# SprinKlr-8_Rev1.net
KiCad netlist of a schematic drawn in EasyEDA Pro
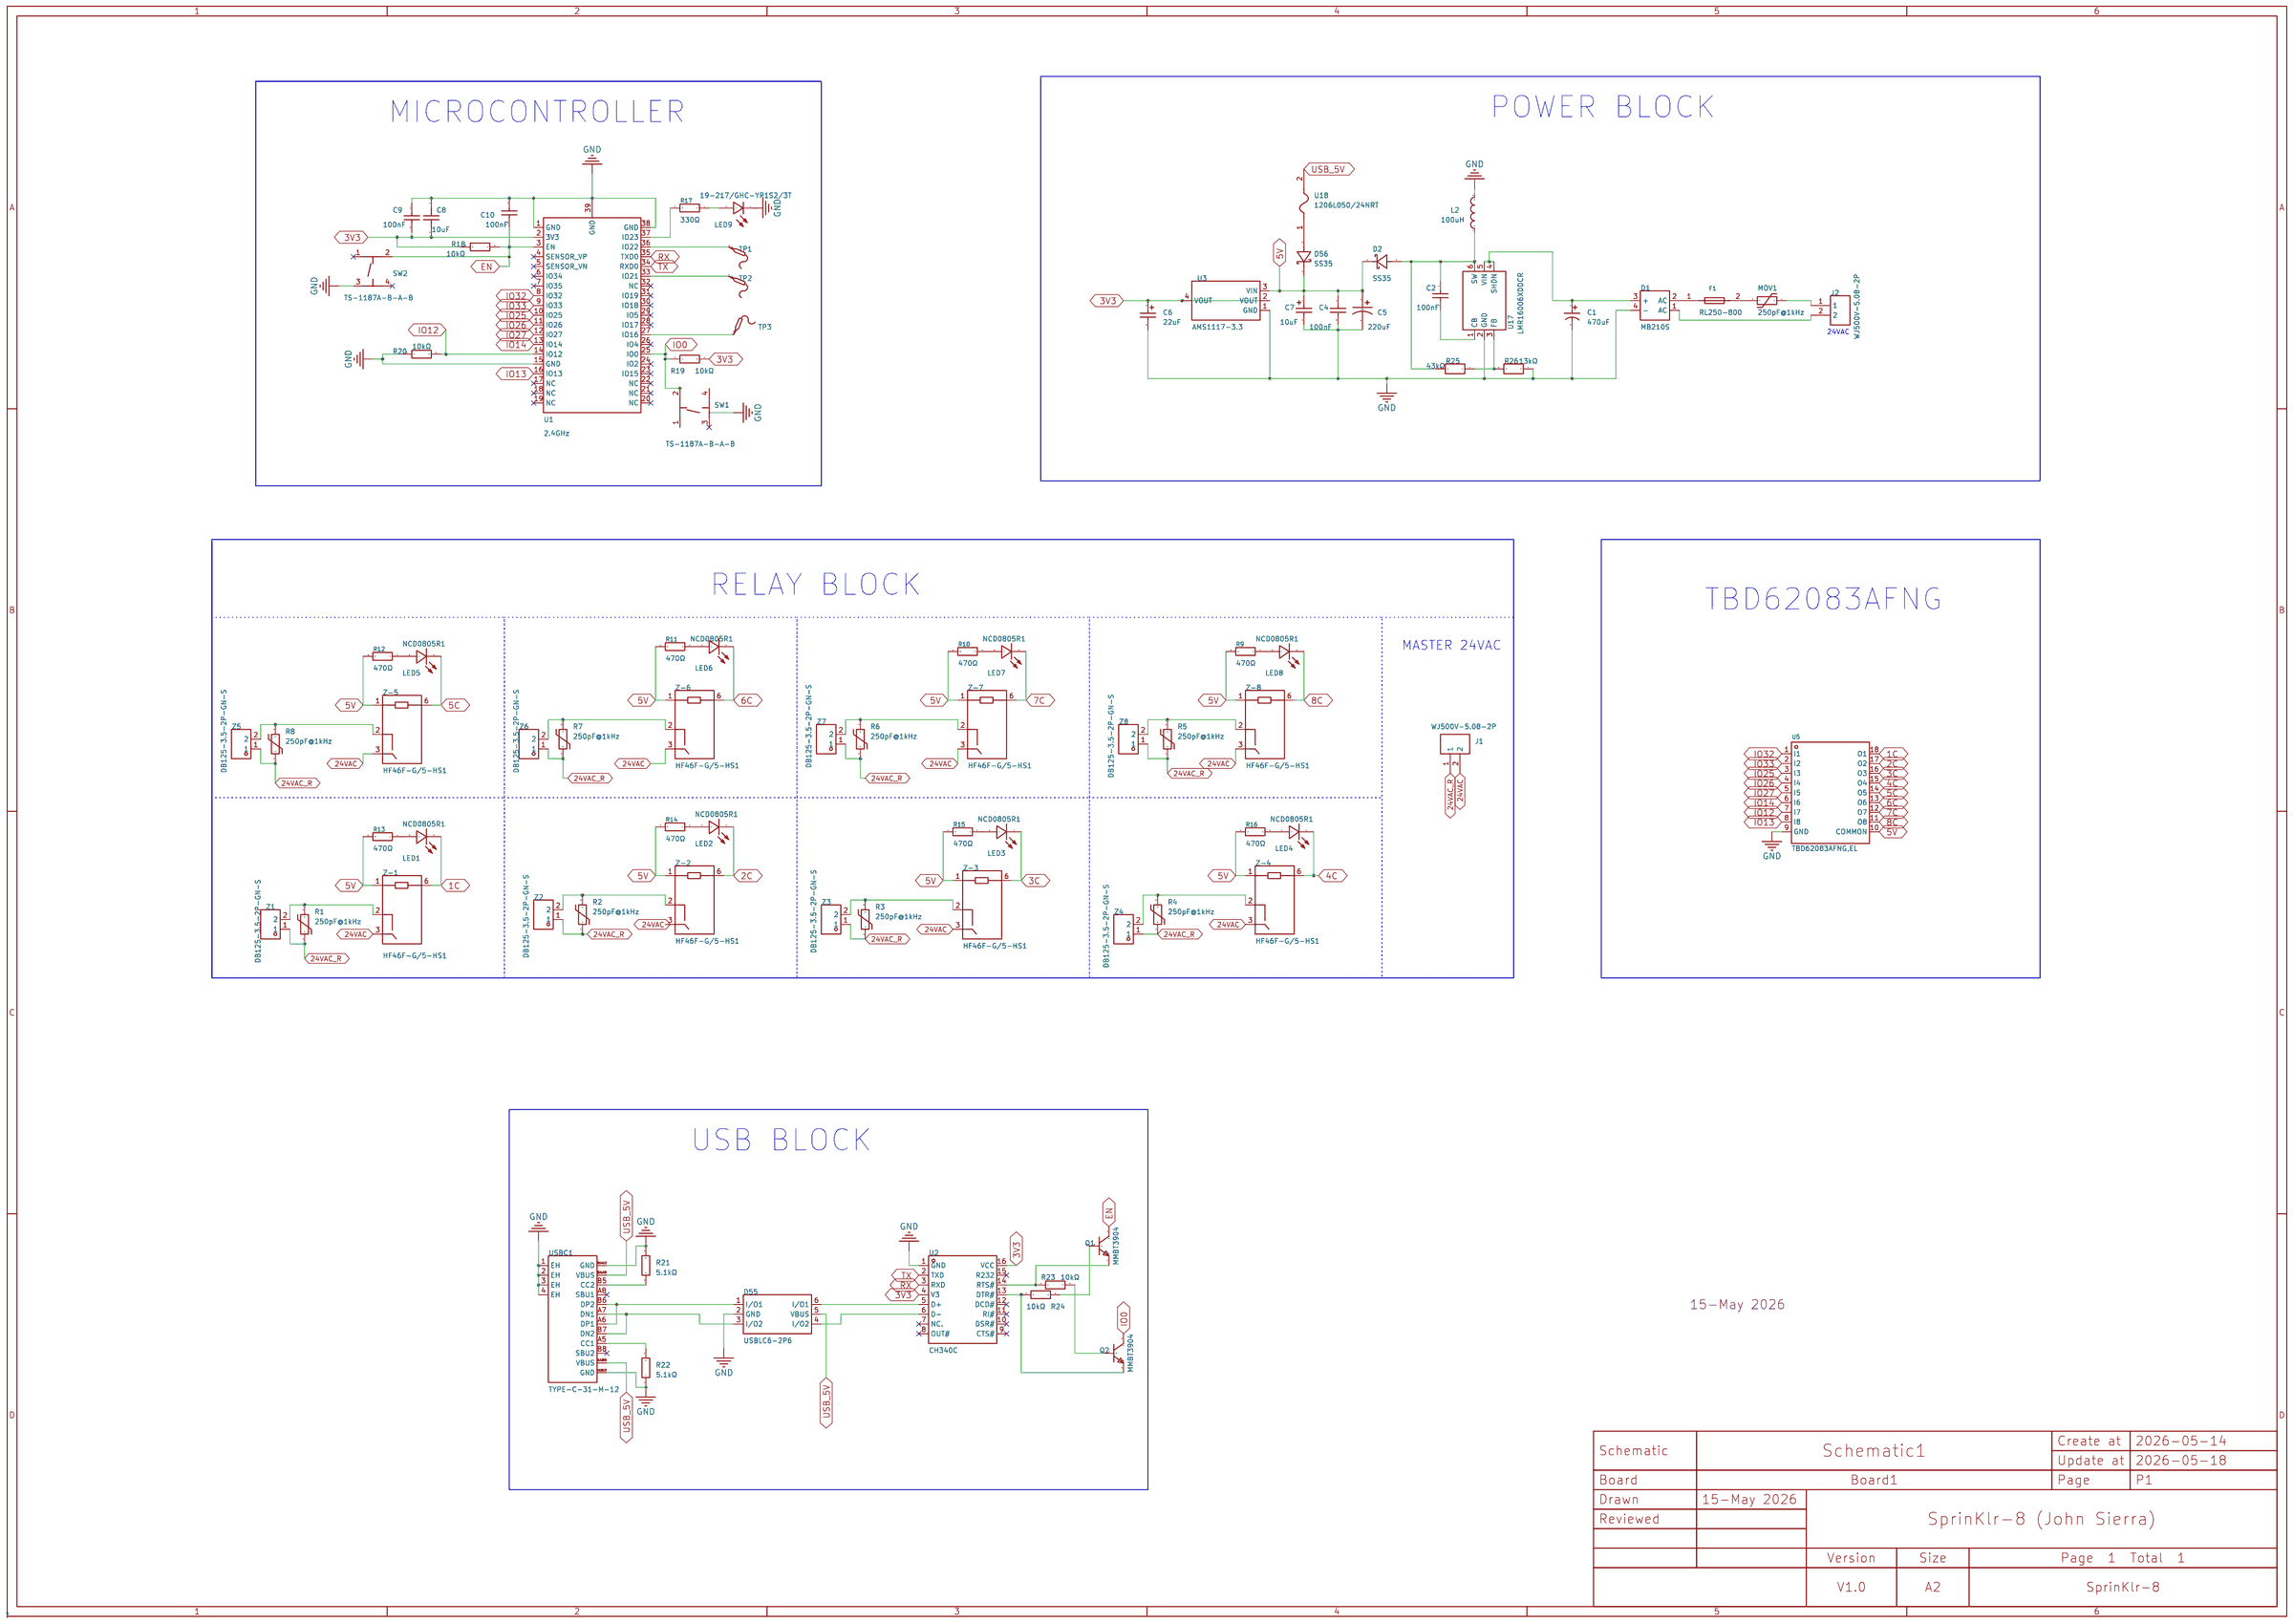
[diagram p0: schematic sheet]

(export (version "E")
  (design (tool "Eeschema 10.0.6"))
  (components
    (comp (ref "C1")
      (value "470uF")
      (footprint "easyedapro:CAP-TH_BD13.0-P5.00-D1.2-FD")
      (fields (field (name "Manufacturer Part") "ERF1HM471K16OT") (field (name "Manufacturer") "AISHI(艾华集团)"))
      (libsource (lib "easyedapro") (part "ERF1HM471K16OT"))
    )
    (comp (ref "C2")
      (value "100nF")
      (footprint "easyedapro:C0805")
      (description "Capacitance:100nF Tolerance:±10% Tolerance:±10% Voltage Rating:100V Temperature Coefficient:X7R")
      (fields
        (field (name "Manufacturer Part") "CL21B104KCFNNNE")
        (field (name "Manufacturer") "SAMSUNG(三星)")
      )
      (libsource (lib "easyedapro") (part "CL21B104KCFNNNE"))
    )
    (comp (ref "C4")
      (value "100nF")
      (footprint "easyedapro:C0805")
      (fields
        (field (name "Manufacturer Part") "CL21B104KCFNNNE")
        (field (name "Manufacturer") "SAMSUNG(三星)")
      )
      (libsource (lib "easyedapro") (part "CL21B104KCFNNNE"))
    )
    (comp (ref "C5")
      (value "220uF")
      (footprint "easyedapro:CAP-TH_BD10.0-P5.00-D1.0-FD")
      (fields
        (field (name "Manufacturer Part") "SHG220UF50V01EC1210")
        (field (name "Manufacturer") "KNSCHA(科尼盛)")
      )
      (libsource (lib "easyedapro") (part "SHG220UF50V01EC1210"))
    )
    (comp (ref "C6")
      (value "22uF")
      (footprint "easyedapro:CASE-A_3216")
      (fields (field (name "Manufacturer Part") "TAJA226K010RNJ") (field (name "Manufacturer") "Kyocera AVX"))
      (libsource (lib "easyedapro") (part "TAJA226K010RNJ"))
    )
    (comp (ref "C7")
      (value "10uF")
      (footprint "easyedapro:CAP-SMD_L3.2-W1.6-RD-C7171")
      (fields (field (name "Manufacturer Part") "TAJA106K016RNJ") (field (name "Manufacturer") "Kyocera AVX"))
      (libsource (lib "easyedapro") (part "TAJA106K016RNJ"))
    )
    (comp (ref "C8")
      (value "10uF")
      (footprint "easyedapro:C0805")
      (fields
        (field (name "Manufacturer Part") "CL21A106KAYNNNE")
        (field (name "Manufacturer") "SAMSUNG(三星)")
      )
      (libsource (lib "easyedapro") (part "CL21A106KAYNNNE"))
    )
    (comp (ref "C9")
      (value "100nF")
      (footprint "easyedapro:C0805")
      (fields
        (field (name "Manufacturer Part") "CL21B104KCFNNNE")
        (field (name "Manufacturer") "SAMSUNG(三星)")
      )
      (libsource (lib "easyedapro") (part "CL21B104KCFNNNE"))
    )
    (comp (ref "C10")
      (value "100nF")
      (footprint "easyedapro:C0805")
      (fields
        (field (name "Manufacturer Part") "CL21B104KCFNNNE")
        (field (name "Manufacturer") "SAMSUNG(三星)")
      )
      (libsource (lib "easyedapro") (part "CL21B104KCFNNNE"))
    )
    (comp (ref "D1")
      (value "MB210S")
      (footprint "easyedapro:MBS_L4.7-W4.0-P2.50-LS7.0-BL")
      (fields (field (name "Manufacturer") "晶导微电子"))
      (libsource (lib "easyedapro") (part "MB210S"))
    )
    (comp (ref "D2")
      (value "SS35")
      (footprint "easyedapro:SMC_L6.9-W5.9-LS7.9-RD")
      (fields (field (name "Manufacturer") "onsemi(安森美)"))
      (libsource (lib "easyedapro") (part "SS35"))
    )
    (comp (ref "D55")
      (value "USBLC6-2P6")
      (footprint "easyedapro:SOT-666-6_L1.6-W1.2-P0.50-LS1.6-BL")
      (fields (field (name "Manufacturer") "TECH PUBLIC(台舟)"))
      (libsource (lib "easyedapro") (part "USBLC6-2P6_C2827693"))
    )
    (comp (ref "D56")
      (value "SS35")
      (footprint "easyedapro:SMC_L6.9-W5.9-LS7.9-RD")
      (fields (field (name "Manufacturer") "onsemi(安森美)"))
      (libsource (lib "easyedapro") (part "SS35"))
    )
    (comp (ref "F1")
      (value "RL250-800")
      (footprint "easyedapro:FUSE-TH_L20.0-W4.5-P5.10-D0.8-S3.70")
      (fields (field (name "Manufacturer") "RUILON(瑞隆源)"))
      (libsource (lib "easyedapro") (part "RL250-800"))
    )
    (comp (ref "J1")
      (value "WJ500V-5.08-2P")
      (footprint "easyedapro:CONN-TH_2P-P5.00_WJ500V-5.08-2P")
      (fields (field (name "Manufacturer") "KANGNEX(康奈克斯电气)"))
      (libsource (lib "easyedapro") (part "WJ500V-5.08-2P-14-00A"))
    )
    (comp (ref "J2")
      (value "WJ500V-5.08-2P")
      (footprint "easyedapro:CONN-TH_2P-P5.00_WJ500V-5.08-2P")
      (fields (field (name "Manufacturer") "KANGNEX(康奈克斯电气)"))
      (libsource (lib "easyedapro") (part "WJ500V-5.08-2P-14-00A"))
    )
    (comp (ref "L2")
      (value "100uH")
      (footprint "easyedapro:IND-SMD_L11.5-W10.0")
      (fields
        (field (name "Manufacturer Part") "PSPMAA1050H-101M-ANP")
        (field (name "Manufacturer") "PROD(谱罗德)")
      )
      (libsource (lib "easyedapro") (part "PSPMAA1050H-101M-ANP"))
    )
    (comp (ref "LED1")
      (value "NCD0805R1")
      (footprint "easyedapro:LED0805-RD")
      (fields (field (name "Manufacturer") "国星光电"))
      (libsource (lib "easyedapro") (part "FC-2012HRK-620D"))
    )
    (comp (ref "LED2")
      (value "NCD0805R1")
      (footprint "easyedapro:LED0805-RD")
      (fields (field (name "Manufacturer") "国星光电"))
      (libsource (lib "easyedapro") (part "FC-2012HRK-620D"))
    )
    (comp (ref "LED3")
      (value "NCD0805R1")
      (footprint "easyedapro:LED0805-RD")
      (fields (field (name "Manufacturer") "国星光电"))
      (libsource (lib "easyedapro") (part "FC-2012HRK-620D"))
    )
    (comp (ref "LED4")
      (value "NCD0805R1")
      (footprint "easyedapro:LED0805-RD")
      (fields (field (name "Manufacturer") "国星光电"))
      (libsource (lib "easyedapro") (part "FC-2012HRK-620D"))
    )
    (comp (ref "LED5")
      (value "NCD0805R1")
      (footprint "easyedapro:LED0805-RD")
      (fields (field (name "Manufacturer") "国星光电"))
      (libsource (lib "easyedapro") (part "FC-2012HRK-620D"))
    )
    (comp (ref "LED6")
      (value "NCD0805R1")
      (footprint "easyedapro:LED0805-RD")
      (fields (field (name "Manufacturer") "国星光电"))
      (libsource (lib "easyedapro") (part "FC-2012HRK-620D"))
    )
    (comp (ref "LED7")
      (value "NCD0805R1")
      (footprint "easyedapro:LED0805-RD")
      (fields (field (name "Manufacturer") "国星光电"))
      (libsource (lib "easyedapro") (part "FC-2012HRK-620D"))
    )
    (comp (ref "LED8")
      (value "NCD0805R1")
      (footprint "easyedapro:LED0805-RD")
      (fields (field (name "Manufacturer") "国星光电"))
      (libsource (lib "easyedapro") (part "FC-2012HRK-620D"))
    )
    (comp (ref "LED9")
      (value "19-217/GHC-YR1S2/3T")
      (footprint "easyedapro:LED0603-RD")
      (fields (field (name "Manufacturer") "EVERLIGHT(亿光)"))
      (libsource (lib "easyedapro") (part "19-217/GHC-YR1S2/3T"))
    )
    (comp (ref "MOV1")
      (value "250pF@1kHz")
      (footprint "easyedapro:RES-TH_L7.5-W4.6-P5.00-D1.2-S2.00")
      (fields
        (field (name "Manufacturer Part") "STE05D101K1BN0FSB0R0")
        (field (name "Manufacturer") "STE(松田)")
      )
      (libsource (lib "easyedapro") (part "STE05D101K1BN0FSB0R0"))
    )
    (comp (ref "Q1")
      (value "MMBT3904")
      (footprint "easyedapro:SOT-23-3_L2.9-W1.3-P1.90-LS2.4-BR")
      (fields (field (name "Manufacturer") "CJ(江苏长电/长晶)"))
      (libsource (lib "easyedapro") (part "MMBT3904"))
    )
    (comp (ref "Q2")
      (value "MMBT3904")
      (footprint "easyedapro:SOT-23-3_L2.9-W1.3-P1.90-LS2.4-BR")
      (fields (field (name "Manufacturer") "CJ(江苏长电/长晶)"))
      (libsource (lib "easyedapro") (part "MMBT3904"))
    )
    (comp (ref "R1")
      (value "250pF@1kHz")
      (footprint "easyedapro:RES-TH_L7.5-W4.6-P5.00-D1.2-S2.00")
      (fields
        (field (name "Manufacturer Part") "STE05D101K1BN0FSB0R0")
        (field (name "Manufacturer") "STE(松田)")
      )
      (libsource (lib "easyedapro") (part "STE05D101K1BN0FSB0R0"))
    )
    (comp (ref "R2")
      (value "250pF@1kHz")
      (footprint "easyedapro:RES-TH_L7.5-W4.6-P5.00-D1.2-S2.00")
      (fields
        (field (name "Manufacturer Part") "STE05D101K1BN0FSB0R0")
        (field (name "Manufacturer") "STE(松田)")
      )
      (libsource (lib "easyedapro") (part "STE05D101K1BN0FSB0R0"))
    )
    (comp (ref "R3")
      (value "250pF@1kHz")
      (footprint "easyedapro:RES-TH_L7.5-W4.6-P5.00-D1.2-S2.00")
      (fields
        (field (name "Manufacturer Part") "STE05D101K1BN0FSB0R0")
        (field (name "Manufacturer") "STE(松田)")
      )
      (libsource (lib "easyedapro") (part "STE05D101K1BN0FSB0R0"))
    )
    (comp (ref "R4")
      (value "250pF@1kHz")
      (footprint "easyedapro:RES-TH_L7.5-W4.6-P5.00-D1.2-S2.00")
      (fields
        (field (name "Manufacturer Part") "STE05D101K1BN0FSB0R0")
        (field (name "Manufacturer") "STE(松田)")
      )
      (libsource (lib "easyedapro") (part "STE05D101K1BN0FSB0R0"))
    )
    (comp (ref "R5")
      (value "250pF@1kHz")
      (footprint "easyedapro:RES-TH_L7.5-W4.6-P5.00-D1.2-S2.00")
      (fields
        (field (name "Manufacturer Part") "STE05D101K1BN0FSB0R0")
        (field (name "Manufacturer") "STE(松田)")
      )
      (libsource (lib "easyedapro") (part "STE05D101K1BN0FSB0R0"))
    )
    (comp (ref "R6")
      (value "250pF@1kHz")
      (footprint "easyedapro:RES-TH_L7.5-W4.6-P5.00-D1.2-S2.00")
      (fields
        (field (name "Manufacturer Part") "STE05D101K1BN0FSB0R0")
        (field (name "Manufacturer") "STE(松田)")
      )
      (libsource (lib "easyedapro") (part "STE05D101K1BN0FSB0R0"))
    )
    (comp (ref "R7")
      (value "250pF@1kHz")
      (footprint "easyedapro:RES-TH_L7.5-W4.6-P5.00-D1.2-S2.00")
      (fields
        (field (name "Manufacturer Part") "STE05D101K1BN0FSB0R0")
        (field (name "Manufacturer") "STE(松田)")
      )
      (libsource (lib "easyedapro") (part "STE05D101K1BN0FSB0R0"))
    )
    (comp (ref "R8")
      (value "250pF@1kHz")
      (footprint "easyedapro:RES-TH_L7.5-W4.6-P5.00-D1.2-S2.00")
      (fields
        (field (name "Manufacturer Part") "STE05D101K1BN0FSB0R0")
        (field (name "Manufacturer") "STE(松田)")
      )
      (libsource (lib "easyedapro") (part "STE05D101K1BN0FSB0R0"))
    )
    (comp (ref "R9")
      (value "470Ω")
      (footprint "easyedapro:R0805")
      (fields
        (field (name "Manufacturer Part") "0805W8F4700T5E")
        (field (name "Manufacturer") "UNI-ROYAL(厚声)")
      )
      (libsource (lib "easyedapro") (part "0805W8F4700T5E"))
    )
    (comp (ref "R10")
      (value "470Ω")
      (footprint "easyedapro:R0805")
      (fields
        (field (name "Manufacturer Part") "0805W8F4700T5E")
        (field (name "Manufacturer") "UNI-ROYAL(厚声)")
      )
      (libsource (lib "easyedapro") (part "0805W8F4700T5E"))
    )
    (comp (ref "R11")
      (value "470Ω")
      (footprint "easyedapro:R0805")
      (fields
        (field (name "Manufacturer Part") "0805W8F4700T5E")
        (field (name "Manufacturer") "UNI-ROYAL(厚声)")
      )
      (libsource (lib "easyedapro") (part "0805W8F4700T5E"))
    )
    (comp (ref "R12")
      (value "470Ω")
      (footprint "easyedapro:R0805")
      (fields
        (field (name "Manufacturer Part") "0805W8F4700T5E")
        (field (name "Manufacturer") "UNI-ROYAL(厚声)")
      )
      (libsource (lib "easyedapro") (part "0805W8F4700T5E"))
    )
    (comp (ref "R13")
      (value "470Ω")
      (footprint "easyedapro:R0805")
      (fields
        (field (name "Manufacturer Part") "0805W8F4700T5E")
        (field (name "Manufacturer") "UNI-ROYAL(厚声)")
      )
      (libsource (lib "easyedapro") (part "0805W8F4700T5E"))
    )
    (comp (ref "R14")
      (value "470Ω")
      (footprint "easyedapro:R0805")
      (fields
        (field (name "Manufacturer Part") "0805W8F4700T5E")
        (field (name "Manufacturer") "UNI-ROYAL(厚声)")
      )
      (libsource (lib "easyedapro") (part "0805W8F4700T5E"))
    )
    (comp (ref "R15")
      (value "470Ω")
      (footprint "easyedapro:R0805")
      (fields
        (field (name "Manufacturer Part") "0805W8F4700T5E")
        (field (name "Manufacturer") "UNI-ROYAL(厚声)")
      )
      (libsource (lib "easyedapro") (part "0805W8F4700T5E"))
    )
    (comp (ref "R16")
      (value "470Ω")
      (footprint "easyedapro:R0805")
      (fields
        (field (name "Manufacturer Part") "0805W8F4700T5E")
        (field (name "Manufacturer") "UNI-ROYAL(厚声)")
      )
      (libsource (lib "easyedapro") (part "0805W8F4700T5E"))
    )
    (comp (ref "R17")
      (value "330Ω")
      (footprint "easyedapro:R0805")
      (fields
        (field (name "Manufacturer Part") "0805W8F3300T5E")
        (field (name "Manufacturer") "UNI-ROYAL(厚声)")
      )
      (libsource (lib "easyedapro") (part "0805W8F3300T5E"))
    )
    (comp (ref "R18")
      (value "10kΩ")
      (footprint "easyedapro:R0402")
      (fields
        (field (name "Manufacturer Part") "0402WGF1002TCE")
        (field (name "Manufacturer") "UNI-ROYAL(厚声)")
      )
      (libsource (lib "easyedapro") (part "0402WGF1002TCE"))
    )
    (comp (ref "R19")
      (value "10kΩ")
      (footprint "easyedapro:R0402")
      (fields
        (field (name "Manufacturer Part") "0402WGF1002TCE")
        (field (name "Manufacturer") "UNI-ROYAL(厚声)")
      )
      (libsource (lib "easyedapro") (part "0402WGF1002TCE"))
    )
    (comp (ref "R20")
      (value "10kΩ")
      (footprint "easyedapro:R0402")
      (fields
        (field (name "Manufacturer Part") "0402WGF1002TCE")
        (field (name "Manufacturer") "UNI-ROYAL(厚声)")
      )
      (libsource (lib "easyedapro") (part "0402WGF1002TCE"))
    )
    (comp (ref "R21")
      (value "5.1kΩ")
      (footprint "easyedapro:R0805")
      (fields
        (field (name "Manufacturer Part") "0805W8F5101T5E")
        (field (name "Manufacturer") "UNI-ROYAL(厚声)")
      )
      (libsource (lib "easyedapro") (part "0805W8F5101T5E"))
    )
    (comp (ref "R22")
      (value "5.1kΩ")
      (footprint "easyedapro:R0805")
      (fields
        (field (name "Manufacturer Part") "0805W8F5101T5E")
        (field (name "Manufacturer") "UNI-ROYAL(厚声)")
      )
      (libsource (lib "easyedapro") (part "0805W8F5101T5E"))
    )
    (comp (ref "R23")
      (value "10kΩ")
      (footprint "easyedapro:R0402")
      (fields
        (field (name "Manufacturer Part") "0402WGF1002TCE")
        (field (name "Manufacturer") "UNI-ROYAL(厚声)")
      )
      (libsource (lib "easyedapro") (part "0402WGF1002TCE"))
    )
    (comp (ref "R24")
      (value "10kΩ")
      (footprint "easyedapro:R0402")
      (fields
        (field (name "Manufacturer Part") "0402WGF1002TCE")
        (field (name "Manufacturer") "UNI-ROYAL(厚声)")
      )
      (libsource (lib "easyedapro") (part "0402WGF1002TCE"))
    )
    (comp (ref "R25")
      (value "43kΩ")
      (footprint "easyedapro:R0603")
      (fields (field (name "Manufacturer Part") "FRC0603F4302TS") (field (name "Manufacturer") "FOJAN(富捷)"))
      (libsource (lib "easyedapro") (part "FRC0603F4302TS"))
    )
    (comp (ref "R26")
      (value "13kΩ")
      (footprint "easyedapro:R0603")
      (fields (field (name "Manufacturer Part") "FRC0603F1302TS") (field (name "Manufacturer") "FOJAN(富捷)"))
      (libsource (lib "easyedapro") (part "FRC0603F1302TS"))
    )
    (comp (ref "SW1")
      (value "TS-1187A-B-A-B")
      (footprint "easyedapro:SW-SMD_4P-L5.1-W5.1-P3.70-LS6.5-TL_H1.5")
      (fields (field (name "Manufacturer") "XKB Connection(中国星坤)"))
      (libsource (lib "easyedapro") (part "TS-1187A-B-A-B"))
    )
    (comp (ref "SW2")
      (value "TS-1187A-B-A-B")
      (footprint "easyedapro:SW-SMD_4P-L5.1-W5.1-P3.70-LS6.5-TL_H1.5")
      (fields (field (name "Manufacturer") "XKB Connection(中国星坤)"))
      (libsource (lib "easyedapro") (part "TS-1187A-B-A-B"))
    )
    (comp (ref "TP1")
      (value "~")
      (footprint "easyedapro:Test-Point-0.5mm")
      (libsource (lib "easyedapro") (part "Test-Point"))
    )
    (comp (ref "TP2")
      (value "~")
      (footprint "easyedapro:Test-Point-0.5mm")
      (libsource (lib "easyedapro") (part "Test-Point"))
    )
    (comp (ref "TP3")
      (value "~")
      (footprint "easyedapro:Test-Point-0.5mm")
      (libsource (lib "easyedapro") (part "Test-Point"))
    )
    (comp (ref "U1")
      (value "2.4GHz")
      (footprint "easyedapro:WIFI-SMD_ESP32-WROOM-32E")
      (fields
        (field (name "Manufacturer Part") "ESP32-WROOM-32E-N4")
        (field (name "Manufacturer") "ESPRESSIF(乐鑫)")
      )
      (libsource (lib "easyedapro") (part "ESP32-WROOM-32E(4MB)"))
    )
    (comp (ref "U2")
      (value "CH340C")
      (footprint "easyedapro:SOP-16_L10.0-W3.9-P1.27-LS6.0-BL")
      (fields (field (name "Manufacturer") "WCH(南京沁恒)"))
      (libsource (lib "easyedapro") (part "CH340C"))
    )
    (comp (ref "U3")
      (value "AMS1117-3.3")
      (footprint "easyedapro:SOT-223-3_L6.5-W3.4-P2.30-LS7.0-BR")
      (fields (field (name "Manufacturer") "AMS"))
      (libsource (lib "easyedapro") (part "AMS1117-3.3"))
    )
    (comp (ref "U5")
      (value "TBD62083AFNG,EL")
      (footprint "easyedapro:SSOP-18_L6.8-W4.4-P0.65-LS6.4-BL")
      (fields (field (name "Manufacturer") "TOSHIBA(东芝)"))
      (libsource (lib "easyedapro") (part "TBD62083AFNG,EL"))
    )
    (comp (ref "U17")
      (value "LMR16006XDDCR")
      (footprint "easyedapro:SOT-23-6_L2.9-W1.6-P0.95-LS2.8-BR")
      (fields (field (name "Manufacturer") "TI(德州仪器)"))
      (libsource (lib "easyedapro") (part "LMR16006XDDCR"))
    )
    (comp (ref "U18")
      (value "1206L050/24NRT")
      (footprint "easyedapro:F1206")
      (fields (field (name "Manufacturer") "LUTE(陆特)"))
      (libsource (lib "easyedapro") (part "1206L050/24NRT"))
    )
    (comp (ref "USBC1")
      (value "TYPE-C-31-M-12")
      (footprint "easyedapro:USB-C_SMD-TYPE-C-31-M-12_1")
      (fields (field (name "Manufacturer") "韩国韩荣"))
      (libsource (lib "easyedapro") (part "TYPE-C-31-M-12"))
    )
    (comp (ref "Z-1")
      (value "HF46F-G/5-HS1")
      (footprint "easyedapro:RELAYS-TH_HF46F-G-XX-HS1-XXX")
      (fields (field (name "Manufacturer") "HF(宏发)"))
      (libsource (lib "easyedapro") (part "HF46F-G/5-HS1"))
    )
    (comp (ref "Z-2")
      (value "HF46F-G/5-HS1")
      (footprint "easyedapro:RELAYS-TH_HF46F-G-XX-HS1-XXX")
      (fields (field (name "Manufacturer") "HF(宏发)"))
      (libsource (lib "easyedapro") (part "HF46F-G/5-HS1"))
    )
    (comp (ref "Z-3")
      (value "HF46F-G/5-HS1")
      (footprint "easyedapro:RELAYS-TH_HF46F-G-XX-HS1-XXX")
      (fields (field (name "Manufacturer") "HF(宏发)"))
      (libsource (lib "easyedapro") (part "HF46F-G/5-HS1"))
    )
    (comp (ref "Z-4")
      (value "HF46F-G/5-HS1")
      (footprint "easyedapro:RELAYS-TH_HF46F-G-XX-HS1-XXX")
      (fields (field (name "Manufacturer") "HF(宏发)"))
      (libsource (lib "easyedapro") (part "HF46F-G/5-HS1"))
    )
    (comp (ref "Z-5")
      (value "HF46F-G/5-HS1")
      (footprint "easyedapro:RELAYS-TH_HF46F-G-XX-HS1-XXX")
      (fields (field (name "Manufacturer") "HF(宏发)"))
      (libsource (lib "easyedapro") (part "HF46F-G/5-HS1"))
    )
    (comp (ref "Z-6")
      (value "HF46F-G/5-HS1")
      (footprint "easyedapro:RELAYS-TH_HF46F-G-XX-HS1-XXX")
      (fields (field (name "Manufacturer") "HF(宏发)"))
      (libsource (lib "easyedapro") (part "HF46F-G/5-HS1"))
    )
    (comp (ref "Z-7")
      (value "HF46F-G/5-HS1")
      (footprint "easyedapro:RELAYS-TH_HF46F-G-XX-HS1-XXX")
      (fields (field (name "Manufacturer") "HF(宏发)"))
      (libsource (lib "easyedapro") (part "HF46F-G/5-HS1"))
    )
    (comp (ref "Z-8")
      (value "HF46F-G/5-HS1")
      (footprint "easyedapro:RELAYS-TH_HF46F-G-XX-HS1-XXX")
      (fields (field (name "Manufacturer") "HF(宏发)"))
      (libsource (lib "easyedapro") (part "HF46F-G/5-HS1"))
    )
    (comp (ref "Z1")
      (value "DB125-3.5-2P-GN-S")
      (footprint "easyedapro:CONN-TH_2P-P3.50_L7.4-W7.0")
      (fields (field (name "Manufacturer") "DORABO(地博电气)"))
      (libsource (lib "easyedapro") (part "DB125-3.5-2P-GN-S"))
    )
    (comp (ref "Z2")
      (value "DB125-3.5-2P-GN-S")
      (footprint "easyedapro:CONN-TH_2P-P3.50_L7.4-W7.0")
      (fields (field (name "Manufacturer") "DORABO(地博电气)"))
      (libsource (lib "easyedapro") (part "DB125-3.5-2P-GN-S"))
    )
    (comp (ref "Z3")
      (value "DB125-3.5-2P-GN-S")
      (footprint "easyedapro:CONN-TH_2P-P3.50_L7.4-W7.0")
      (fields (field (name "Manufacturer") "DORABO(地博电气)"))
      (libsource (lib "easyedapro") (part "DB125-3.5-2P-GN-S"))
    )
    (comp (ref "Z4")
      (value "DB125-3.5-2P-GN-S")
      (footprint "easyedapro:CONN-TH_2P-P3.50_L7.4-W7.0")
      (fields (field (name "Manufacturer") "DORABO(地博电气)"))
      (libsource (lib "easyedapro") (part "DB125-3.5-2P-GN-S"))
    )
    (comp (ref "Z5")
      (value "DB125-3.5-2P-GN-S")
      (footprint "easyedapro:CONN-TH_2P-P3.50_L7.4-W7.0")
      (fields (field (name "Manufacturer") "DORABO(地博电气)"))
      (libsource (lib "easyedapro") (part "DB125-3.5-2P-GN-S"))
    )
    (comp (ref "Z6")
      (value "DB125-3.5-2P-GN-S")
      (footprint "easyedapro:CONN-TH_2P-P3.50_L7.4-W7.0")
      (fields (field (name "Manufacturer") "DORABO(地博电气)"))
      (libsource (lib "easyedapro") (part "DB125-3.5-2P-GN-S"))
    )
    (comp (ref "Z7")
      (value "DB125-3.5-2P-GN-S")
      (footprint "easyedapro:CONN-TH_2P-P3.50_L7.4-W7.0")
      (fields (field (name "Manufacturer") "DORABO(地博电气)"))
      (libsource (lib "easyedapro") (part "DB125-3.5-2P-GN-S"))
    )
    (comp (ref "Z8")
      (value "DB125-3.5-2P-GN-S")
      (footprint "easyedapro:CONN-TH_2P-P3.50_L7.4-W7.0")
      (fields (field (name "Manufacturer") "DORABO(地博电气)"))
      (libsource (lib "easyedapro") (part "DB125-3.5-2P-GN-S"))
    )
  )
  (nets
    (net (code "1") (name "1C") (class "Default")
      (node (ref "LED1") (pin "1") (pinfunction "-_1") (pintype "unspecified"))
      (node (ref "U5") (pin "18") (pinfunction "O1_18") (pintype "input"))
      (node (ref "Z-1") (pin "6") (pinfunction "6_6") (pintype "unspecified"))
    )
    (net (code "2") (name "2C") (class "Default")
      (node (ref "LED2") (pin "1") (pinfunction "-_1") (pintype "unspecified"))
      (node (ref "U5") (pin "17") (pinfunction "O2_17") (pintype "input"))
      (node (ref "Z-2") (pin "6") (pinfunction "6_6") (pintype "unspecified"))
    )
    (net (code "3") (name "3C") (class "Default")
      (node (ref "LED3") (pin "1") (pinfunction "-_1") (pintype "unspecified"))
      (node (ref "U5") (pin "16") (pinfunction "O3_16") (pintype "input"))
      (node (ref "Z-3") (pin "6") (pinfunction "6_6") (pintype "unspecified"))
    )
    (net (code "4") (name "3V3") (class "Default")
      (node (ref "C6") (pin "1") (pinfunction "1_1") (pintype "input"))
      (node (ref "C8") (pin "2") (pinfunction "2_2") (pintype "unspecified"))
      (node (ref "C9") (pin "2") (pinfunction "2_2") (pintype "input"))
      (node (ref "R18") (pin "1") (pinfunction "1_1") (pintype "input"))
      (node (ref "R19") (pin "2") (pinfunction "2_2") (pintype "input"))
      (node (ref "U1") (pin "2") (pinfunction "3V3_2") (pintype "unspecified"))
      (node (ref "U2") (pin "16") (pinfunction "VCC_16") (pintype "unspecified"))
      (node (ref "U2") (pin "4") (pinfunction "V3_4") (pintype "unspecified"))
      (node (ref "U3") (pin "2") (pinfunction "VOUT_2") (pintype "unspecified"))
      (node (ref "U3") (pin "4") (pinfunction "VOUT_4") (pintype "unspecified"))
    )
    (net (code "5") (name "4C") (class "Default")
      (node (ref "LED4") (pin "1") (pinfunction "-_1") (pintype "unspecified"))
      (node (ref "U5") (pin "15") (pinfunction "O4_15") (pintype "input"))
      (node (ref "Z-4") (pin "6") (pinfunction "6_6") (pintype "unspecified"))
    )
    (net (code "6") (name "5C") (class "Default")
      (node (ref "LED5") (pin "1") (pinfunction "-_1") (pintype "unspecified"))
      (node (ref "U5") (pin "14") (pinfunction "O5_14") (pintype "input"))
      (node (ref "Z-5") (pin "6") (pinfunction "6_6") (pintype "unspecified"))
    )
    (net (code "7") (name "5V") (class "Default")
      (node (ref "C4") (pin "1") (pinfunction "1_1") (pintype "input"))
      (node (ref "C5") (pin "1") (pinfunction "1_1") (pintype "unspecified"))
      (node (ref "C7") (pin "1") (pinfunction "1_1") (pintype "input"))
      (node (ref "D2") (pin "1") (pinfunction "C_1") (pintype "unspecified"))
      (node (ref "D56") (pin "1") (pinfunction "C_1") (pintype "unspecified"))
      (node (ref "R10") (pin "2") (pinfunction "2_2") (pintype "input"))
      (node (ref "R11") (pin "2") (pinfunction "2_2") (pintype "input"))
      (node (ref "R12") (pin "2") (pinfunction "2_2") (pintype "input"))
      (node (ref "R13") (pin "2") (pinfunction "2_2") (pintype "input"))
      (node (ref "R14") (pin "2") (pinfunction "2_2") (pintype "input"))
      (node (ref "R15") (pin "2") (pinfunction "2_2") (pintype "input"))
      (node (ref "R16") (pin "2") (pinfunction "2_2") (pintype "input"))
      (node (ref "R9") (pin "2") (pinfunction "2_2") (pintype "input"))
      (node (ref "U3") (pin "3") (pinfunction "VIN_3") (pintype "unspecified"))
      (node (ref "U5") (pin "10") (pinfunction "COMMON_10") (pintype "input"))
      (node (ref "Z-1") (pin "1") (pinfunction "1_1") (pintype "unspecified"))
      (node (ref "Z-2") (pin "1") (pinfunction "1_1") (pintype "unspecified"))
      (node (ref "Z-3") (pin "1") (pinfunction "1_1") (pintype "unspecified"))
      (node (ref "Z-4") (pin "1") (pinfunction "1_1") (pintype "unspecified"))
      (node (ref "Z-5") (pin "1") (pinfunction "1_1") (pintype "unspecified"))
      (node (ref "Z-6") (pin "1") (pinfunction "1_1") (pintype "unspecified"))
      (node (ref "Z-7") (pin "1") (pinfunction "1_1") (pintype "unspecified"))
      (node (ref "Z-8") (pin "1") (pinfunction "1_1") (pintype "unspecified"))
    )
    (net (code "8") (name "6C") (class "Default")
      (node (ref "LED6") (pin "1") (pinfunction "-_1") (pintype "unspecified"))
      (node (ref "U5") (pin "13") (pinfunction "O6_13") (pintype "input"))
      (node (ref "Z-6") (pin "6") (pinfunction "6_6") (pintype "unspecified"))
    )
    (net (code "9") (name "7C") (class "Default")
      (node (ref "LED7") (pin "1") (pinfunction "-_1") (pintype "unspecified"))
      (node (ref "U5") (pin "12") (pinfunction "O7_12") (pintype "input"))
      (node (ref "Z-7") (pin "6") (pinfunction "6_6") (pintype "unspecified"))
    )
    (net (code "10") (name "8C") (class "Default")
      (node (ref "LED8") (pin "1") (pinfunction "-_1") (pintype "unspecified"))
      (node (ref "U5") (pin "11") (pinfunction "O8_11") (pintype "input"))
      (node (ref "Z-8") (pin "6") (pinfunction "6_6") (pintype "unspecified"))
    )
    (net (code "11") (name "24VAC") (class "Default")
      (node (ref "J1") (pin "2") (pinfunction "2_2") (pintype "unspecified"))
      (node (ref "Z-1") (pin "3") (pinfunction "3_3") (pintype "unspecified"))
      (node (ref "Z-2") (pin "3") (pinfunction "3_3") (pintype "unspecified"))
      (node (ref "Z-3") (pin "3") (pinfunction "3_3") (pintype "unspecified"))
      (node (ref "Z-4") (pin "3") (pinfunction "3_3") (pintype "unspecified"))
      (node (ref "Z-5") (pin "3") (pinfunction "3_3") (pintype "unspecified"))
      (node (ref "Z-6") (pin "3") (pinfunction "3_3") (pintype "unspecified"))
      (node (ref "Z-7") (pin "3") (pinfunction "3_3") (pintype "unspecified"))
      (node (ref "Z-8") (pin "3") (pinfunction "3_3") (pintype "unspecified"))
    )
    (net (code "12") (name "24VAC_R") (class "Default")
      (node (ref "J1") (pin "1") (pinfunction "1_1") (pintype "unspecified"))
      (node (ref "R1") (pin "1") (pinfunction "1_1") (pintype "unspecified"))
      (node (ref "R2") (pin "1") (pinfunction "1_1") (pintype "unspecified"))
      (node (ref "R3") (pin "1") (pinfunction "1_1") (pintype "unspecified"))
      (node (ref "R4") (pin "1") (pinfunction "1_1") (pintype "unspecified"))
      (node (ref "R5") (pin "1") (pinfunction "1_1") (pintype "unspecified"))
      (node (ref "R6") (pin "1") (pinfunction "1_1") (pintype "unspecified"))
      (node (ref "R7") (pin "1") (pinfunction "1_1") (pintype "unspecified"))
      (node (ref "R8") (pin "1") (pinfunction "1_1") (pintype "unspecified"))
      (node (ref "Z1") (pin "1") (pinfunction "1_1") (pintype "unspecified"))
      (node (ref "Z2") (pin "1") (pinfunction "1_1") (pintype "unspecified"))
      (node (ref "Z3") (pin "1") (pinfunction "1_1") (pintype "unspecified"))
      (node (ref "Z4") (pin "1") (pinfunction "1_1") (pintype "unspecified"))
      (node (ref "Z5") (pin "1") (pinfunction "1_1") (pintype "unspecified"))
      (node (ref "Z6") (pin "1") (pinfunction "1_1") (pintype "unspecified"))
      (node (ref "Z7") (pin "1") (pinfunction "1_1") (pintype "unspecified"))
      (node (ref "Z8") (pin "1") (pinfunction "1_1") (pintype "unspecified"))
    )
    (net (code "13") (name "EN") (class "Default")
      (node (ref "C10") (pin "2") (pinfunction "2_2") (pintype "input"))
      (node (ref "Q1") (pin "3") (pinfunction "C_3") (pintype "unspecified"))
      (node (ref "R18") (pin "2") (pinfunction "2_2") (pintype "input"))
      (node (ref "SW2") (pin "2") (pinfunction "B_2") (pintype "unspecified"))
      (node (ref "U1") (pin "3") (pinfunction "EN_3") (pintype "unspecified"))
    )
    (net (code "14") (name "GND") (class "Default")
      (node (ref "C1") (pin "2") (pinfunction "2_2") (pintype "input"))
      (node (ref "C10") (pin "1") (pinfunction "1_1") (pintype "input"))
      (node (ref "C4") (pin "2") (pinfunction "2_2") (pintype "input"))
      (node (ref "C5") (pin "2") (pinfunction "2_2") (pintype "unspecified"))
      (node (ref "C6") (pin "2") (pinfunction "2_2") (pintype "input"))
      (node (ref "C7") (pin "2") (pinfunction "2_2") (pintype "input"))
      (node (ref "C8") (pin "1") (pinfunction "1_1") (pintype "unspecified"))
      (node (ref "C9") (pin "1") (pinfunction "1_1") (pintype "input"))
      (node (ref "D1") (pin "4") (pinfunction "-_4") (pintype "unspecified"))
      (node (ref "D55") (pin "2") (pinfunction "GND_2") (pintype "unspecified"))
      (node (ref "L2") (pin "2") (pinfunction "2_2") (pintype "unspecified"))
      (node (ref "LED9") (pin "1") (pinfunction "C_1") (pintype "input"))
      (node (ref "R20") (pin "1") (pinfunction "1_1") (pintype "input"))
      (node (ref "R21") (pin "2") (pinfunction "2_2") (pintype "input"))
      (node (ref "R22") (pin "1") (pinfunction "1_1") (pintype "input"))
      (node (ref "R26") (pin "1") (pinfunction "1_1") (pintype "unspecified"))
      (node (ref "SW1") (pin "4") (pinfunction "D_4") (pintype "unspecified"))
      (node (ref "SW2") (pin "3") (pinfunction "C_3") (pintype "unspecified"))
      (node (ref "U1") (pin "1") (pinfunction "GND_1") (pintype "unspecified"))
      (node (ref "U1") (pin "15") (pinfunction "GND_15") (pintype "unspecified"))
      (node (ref "U1") (pin "38") (pinfunction "GND_38") (pintype "unspecified"))
      (node (ref "U1") (pin "39") (pinfunction "GND_39") (pintype "unspecified"))
      (node (ref "U17") (pin "2") (pinfunction "GND_2") (pintype "unspecified"))
      (node (ref "U2") (pin "1") (pinfunction "GND_1") (pintype "unspecified"))
      (node (ref "U3") (pin "1") (pinfunction "GND_1") (pintype "unspecified"))
      (node (ref "U5") (pin "9") (pinfunction "GND_9") (pintype "input"))
      (node (ref "USBC1") (pin "1") (pinfunction "EH_1") (pintype "unspecified"))
      (node (ref "USBC1") (pin "2") (pinfunction "EH_2") (pintype "unspecified"))
      (node (ref "USBC1") (pin "3") (pinfunction "EH_3") (pintype "unspecified"))
      (node (ref "USBC1") (pin "4") (pinfunction "EH_4") (pintype "unspecified"))
      (node (ref "USBC1") (pin "A1B12") (pinfunction "GND_A1B12") (pintype "unspecified"))
      (node (ref "USBC1") (pin "B1A12") (pinfunction "GND_B1A12") (pintype "unspecified"))
    )
    (net (code "15") (name "IO0") (class "Default")
      (node (ref "Q2") (pin "3") (pinfunction "C_3") (pintype "unspecified"))
      (node (ref "R19") (pin "1") (pinfunction "1_1") (pintype "input"))
      (node (ref "SW1") (pin "1") (pinfunction "A_1") (pintype "unspecified"))
      (node (ref "SW1") (pin "2") (pinfunction "B_2") (pintype "unspecified"))
      (node (ref "U1") (pin "25") (pinfunction "IO0_25") (pintype "unspecified"))
    )
    (net (code "16") (name "IO12") (class "Default")
      (node (ref "R20") (pin "2") (pinfunction "2_2") (pintype "input"))
      (node (ref "U1") (pin "14") (pinfunction "IO12_14") (pintype "unspecified"))
      (node (ref "U5") (pin "7") (pinfunction "I7_7") (pintype "input"))
    )
    (net (code "17") (name "IO13") (class "Default")
      (node (ref "U1") (pin "16") (pinfunction "IO13_16") (pintype "unspecified"))
      (node (ref "U5") (pin "8") (pinfunction "I8_8") (pintype "input"))
    )
    (net (code "18") (name "IO14") (class "Default")
      (node (ref "U1") (pin "13") (pinfunction "IO14_13") (pintype "unspecified"))
      (node (ref "U5") (pin "6") (pinfunction "I6_6") (pintype "input"))
    )
    (net (code "19") (name "IO25") (class "Default")
      (node (ref "U1") (pin "10") (pinfunction "IO25_10") (pintype "unspecified"))
      (node (ref "U5") (pin "3") (pinfunction "I3_3") (pintype "input"))
    )
    (net (code "20") (name "IO26") (class "Default")
      (node (ref "U1") (pin "11") (pinfunction "IO26_11") (pintype "unspecified"))
      (node (ref "U5") (pin "4") (pinfunction "I4_4") (pintype "input"))
    )
    (net (code "21") (name "IO27") (class "Default")
      (node (ref "U1") (pin "12") (pinfunction "IO27_12") (pintype "unspecified"))
      (node (ref "U5") (pin "5") (pinfunction "I5_5") (pintype "input"))
    )
    (net (code "22") (name "IO32") (class "Default")
      (node (ref "U1") (pin "8") (pinfunction "IO32_8") (pintype "unspecified"))
      (node (ref "U5") (pin "1") (pinfunction "I1_1") (pintype "input"))
    )
    (net (code "23") (name "IO33") (class "Default")
      (node (ref "U1") (pin "9") (pinfunction "IO33_9") (pintype "unspecified"))
      (node (ref "U5") (pin "2") (pinfunction "I2_2") (pintype "input"))
    )
    (net (code "24") (name "Net-(D1-+)") (class "Default")
      (node (ref "C1") (pin "1") (pinfunction "1_1") (pintype "input"))
      (node (ref "D1") (pin "3") (pinfunction "+_3") (pintype "unspecified"))
      (node (ref "U17") (pin "4") (pinfunction "SHDN_4") (pintype "unspecified"))
      (node (ref "U17") (pin "5") (pinfunction "VIN_5") (pintype "unspecified"))
    )
    (net (code "25") (name "Net-(D1-AC-Pad1)") (class "Default")
      (node (ref "D1") (pin "1") (pinfunction "AC_1") (pintype "unspecified"))
      (node (ref "J2") (pin "2") (pinfunction "2_2") (pintype "unspecified"))
    )
    (net (code "26") (name "Net-(D1-AC-Pad2)") (class "Default")
      (node (ref "D1") (pin "2") (pinfunction "AC_2") (pintype "unspecified"))
      (node (ref "F1") (pin "1") (pinfunction "1_1") (pintype "input"))
    )
    (net (code "27") (name "Net-(D2-A)") (class "Default")
      (node (ref "C2") (pin "1") (pinfunction "1_1") (pintype "input"))
      (node (ref "D2") (pin "2") (pinfunction "A_2") (pintype "unspecified"))
      (node (ref "L2") (pin "1") (pinfunction "1_1") (pintype "unspecified"))
      (node (ref "R25") (pin "2") (pinfunction "2_2") (pintype "unspecified"))
      (node (ref "U17") (pin "6") (pinfunction "SW_6") (pintype "unspecified"))
    )
    (net (code "28") (name "Net-(D56-A)") (class "Default")
      (node (ref "D56") (pin "2") (pinfunction "A_2") (pintype "unspecified"))
      (node (ref "U18") (pin "1") (pinfunction "1_1") (pintype "unspecified"))
    )
    (net (code "29") (name "Net-(F1-Pad2)") (class "Default")
      (node (ref "F1") (pin "2") (pinfunction "2_2") (pintype "input"))
      (node (ref "MOV1") (pin "2") (pinfunction "2_2") (pintype "unspecified"))
    )
    (net (code "30") (name "Net-(J2-Pad1)") (class "Default")
      (node (ref "J2") (pin "1") (pinfunction "1_1") (pintype "unspecified"))
      (node (ref "MOV1") (pin "1") (pinfunction "1_1") (pintype "unspecified"))
    )
    (net (code "31") (name "Net-(LED1-+)") (class "Default")
      (node (ref "LED1") (pin "2") (pinfunction "+_2") (pintype "unspecified"))
      (node (ref "R13") (pin "1") (pinfunction "1_1") (pintype "input"))
    )
    (net (code "32") (name "Net-(LED2-+)") (class "Default")
      (node (ref "LED2") (pin "2") (pinfunction "+_2") (pintype "unspecified"))
      (node (ref "R14") (pin "1") (pinfunction "1_1") (pintype "input"))
    )
    (net (code "33") (name "Net-(LED3-+)") (class "Default")
      (node (ref "LED3") (pin "2") (pinfunction "+_2") (pintype "unspecified"))
      (node (ref "R15") (pin "1") (pinfunction "1_1") (pintype "input"))
    )
    (net (code "34") (name "Net-(LED4-+)") (class "Default")
      (node (ref "LED4") (pin "2") (pinfunction "+_2") (pintype "unspecified"))
      (node (ref "R16") (pin "1") (pinfunction "1_1") (pintype "input"))
    )
    (net (code "35") (name "Net-(LED5-+)") (class "Default")
      (node (ref "LED5") (pin "2") (pinfunction "+_2") (pintype "unspecified"))
      (node (ref "R12") (pin "1") (pinfunction "1_1") (pintype "input"))
    )
    (net (code "36") (name "Net-(LED6-+)") (class "Default")
      (node (ref "LED6") (pin "2") (pinfunction "+_2") (pintype "unspecified"))
      (node (ref "R11") (pin "1") (pinfunction "1_1") (pintype "input"))
    )
    (net (code "37") (name "Net-(LED7-+)") (class "Default")
      (node (ref "LED7") (pin "2") (pinfunction "+_2") (pintype "unspecified"))
      (node (ref "R10") (pin "1") (pinfunction "1_1") (pintype "input"))
    )
    (net (code "38") (name "Net-(LED8-+)") (class "Default")
      (node (ref "LED8") (pin "2") (pinfunction "+_2") (pintype "unspecified"))
      (node (ref "R9") (pin "1") (pinfunction "1_1") (pintype "input"))
    )
    (net (code "39") (name "Net-(LED9-A)") (class "Default")
      (node (ref "LED9") (pin "2") (pinfunction "A_2") (pintype "input"))
      (node (ref "R17") (pin "1") (pinfunction "1_1") (pintype "input"))
    )
    (net (code "40") (name "Net-(Q1-B)") (class "Default")
      (node (ref "Q1") (pin "1") (pinfunction "B_1") (pintype "unspecified"))
      (node (ref "R24") (pin "2") (pinfunction "2_2") (pintype "input"))
    )
    (net (code "41") (name "Net-(Q1-E)") (class "Default")
      (node (ref "Q1") (pin "2") (pinfunction "E_2") (pintype "unspecified"))
      (node (ref "R23") (pin "1") (pinfunction "1_1") (pintype "input"))
      (node (ref "U2") (pin "14") (pinfunction "RTS#_14") (pintype "unspecified"))
    )
    (net (code "42") (name "Net-(Q2-B)") (class "Default")
      (node (ref "Q2") (pin "1") (pinfunction "B_1") (pintype "unspecified"))
      (node (ref "R23") (pin "2") (pinfunction "2_2") (pintype "input"))
    )
    (net (code "43") (name "Net-(Q2-E)") (class "Default")
      (node (ref "Q2") (pin "2") (pinfunction "E_2") (pintype "unspecified"))
      (node (ref "R24") (pin "1") (pinfunction "1_1") (pintype "input"))
      (node (ref "U2") (pin "13") (pinfunction "DTR#_13") (pintype "unspecified"))
    )
    (net (code "44") (name "Net-(R1-Pad2)") (class "Default")
      (node (ref "R1") (pin "2") (pinfunction "2_2") (pintype "unspecified"))
      (node (ref "Z-1") (pin "2") (pinfunction "2_2") (pintype "unspecified"))
      (node (ref "Z1") (pin "2") (pinfunction "2_2") (pintype "unspecified"))
    )
    (net (code "45") (name "Net-(R2-Pad2)") (class "Default")
      (node (ref "R2") (pin "2") (pinfunction "2_2") (pintype "unspecified"))
      (node (ref "Z-2") (pin "2") (pinfunction "2_2") (pintype "unspecified"))
      (node (ref "Z2") (pin "2") (pinfunction "2_2") (pintype "unspecified"))
    )
    (net (code "46") (name "Net-(R3-Pad2)") (class "Default")
      (node (ref "R3") (pin "2") (pinfunction "2_2") (pintype "unspecified"))
      (node (ref "Z-3") (pin "2") (pinfunction "2_2") (pintype "unspecified"))
      (node (ref "Z3") (pin "2") (pinfunction "2_2") (pintype "unspecified"))
    )
    (net (code "47") (name "Net-(R4-Pad2)") (class "Default")
      (node (ref "R4") (pin "2") (pinfunction "2_2") (pintype "unspecified"))
      (node (ref "Z-4") (pin "2") (pinfunction "2_2") (pintype "unspecified"))
      (node (ref "Z4") (pin "2") (pinfunction "2_2") (pintype "unspecified"))
    )
    (net (code "48") (name "Net-(R5-Pad2)") (class "Default")
      (node (ref "R5") (pin "2") (pinfunction "2_2") (pintype "unspecified"))
      (node (ref "Z-8") (pin "2") (pinfunction "2_2") (pintype "unspecified"))
      (node (ref "Z8") (pin "2") (pinfunction "2_2") (pintype "unspecified"))
    )
    (net (code "49") (name "Net-(R6-Pad2)") (class "Default")
      (node (ref "R6") (pin "2") (pinfunction "2_2") (pintype "unspecified"))
      (node (ref "Z-7") (pin "2") (pinfunction "2_2") (pintype "unspecified"))
      (node (ref "Z7") (pin "2") (pinfunction "2_2") (pintype "unspecified"))
    )
    (net (code "50") (name "Net-(R7-Pad2)") (class "Default")
      (node (ref "R7") (pin "2") (pinfunction "2_2") (pintype "unspecified"))
      (node (ref "Z-6") (pin "2") (pinfunction "2_2") (pintype "unspecified"))
      (node (ref "Z6") (pin "2") (pinfunction "2_2") (pintype "unspecified"))
    )
    (net (code "51") (name "Net-(R8-Pad2)") (class "Default")
      (node (ref "R8") (pin "2") (pinfunction "2_2") (pintype "unspecified"))
      (node (ref "Z-5") (pin "2") (pinfunction "2_2") (pintype "unspecified"))
      (node (ref "Z5") (pin "2") (pinfunction "2_2") (pintype "unspecified"))
    )
    (net (code "52") (name "Net-(U1-IO16)") (class "Default")
      (node (ref "TP3") (pin "1") (pinfunction "1_1") (pintype "unspecified"))
      (node (ref "U1") (pin "27") (pinfunction "IO16_27") (pintype "unspecified"))
    )
    (net (code "53") (name "Net-(U1-IO21)") (class "Default")
      (node (ref "TP2") (pin "1") (pinfunction "1_1") (pintype "unspecified"))
      (node (ref "U1") (pin "33") (pinfunction "IO21_33") (pintype "unspecified"))
    )
    (net (code "54") (name "Net-(U1-IO22)") (class "Default")
      (node (ref "TP1") (pin "1") (pinfunction "1_1") (pintype "unspecified"))
      (node (ref "U1") (pin "36") (pinfunction "IO22_36") (pintype "unspecified"))
    )
    (net (code "55") (name "Net-(U1-IO23)") (class "Default")
      (node (ref "R17") (pin "2") (pinfunction "2_2") (pintype "input"))
      (node (ref "U1") (pin "37") (pinfunction "IO23_37") (pintype "unspecified"))
    )
    (net (code "56") (name "Net-(U2-D+)") (class "Default")
      (node (ref "D55") (pin "6") (pinfunction "I/O1_6") (pintype "unspecified"))
      (node (ref "U2") (pin "5") (pinfunction "D+_5") (pintype "unspecified"))
    )
    (net (code "57") (name "Net-(U2-D-)") (class "Default")
      (node (ref "D55") (pin "4") (pinfunction "I/O2_4") (pintype "unspecified"))
      (node (ref "U2") (pin "6") (pinfunction "D-_6") (pintype "unspecified"))
    )
    (net (code "58") (name "Net-(U17-CB)") (class "Default")
      (node (ref "C2") (pin "2") (pinfunction "2_2") (pintype "input"))
      (node (ref "U17") (pin "1") (pinfunction "CB_1") (pintype "unspecified"))
    )
    (net (code "59") (name "Net-(U17-FB)") (class "Default")
      (node (ref "R25") (pin "1") (pinfunction "1_1") (pintype "unspecified"))
      (node (ref "R26") (pin "2") (pinfunction "2_2") (pintype "unspecified"))
      (node (ref "U17") (pin "3") (pinfunction "FB_3") (pintype "unspecified"))
    )
    (net (code "60") (name "Net-(USBC1-CC1)") (class "Default")
      (node (ref "R22") (pin "2") (pinfunction "2_2") (pintype "input"))
      (node (ref "USBC1") (pin "A5") (pinfunction "CC1_A5") (pintype "unspecified"))
    )
    (net (code "61") (name "Net-(USBC1-CC2)") (class "Default")
      (node (ref "R21") (pin "1") (pinfunction "1_1") (pintype "input"))
      (node (ref "USBC1") (pin "B5") (pinfunction "CC2_B5") (pintype "unspecified"))
    )
    (net (code "62") (name "Net-(USBC1-DN1)") (class "Default")
      (node (ref "D55") (pin "3") (pinfunction "I/O2_3") (pintype "unspecified"))
      (node (ref "USBC1") (pin "A7") (pinfunction "DN1_A7") (pintype "unspecified"))
      (node (ref "USBC1") (pin "B7") (pinfunction "DN2_B7") (pintype "unspecified"))
    )
    (net (code "63") (name "Net-(USBC1-DP1)") (class "Default")
      (node (ref "D55") (pin "1") (pinfunction "I/O1_1") (pintype "unspecified"))
      (node (ref "USBC1") (pin "A6") (pinfunction "DP1_A6") (pintype "unspecified"))
      (node (ref "USBC1") (pin "B6") (pinfunction "DP2_B6") (pintype "unspecified"))
    )
    (net (code "64") (name "RX") (class "Default")
      (node (ref "U1") (pin "35") (pinfunction "TXD0_35") (pintype "unspecified"))
      (node (ref "U2") (pin "3") (pinfunction "RXD_3") (pintype "unspecified"))
    )
    (net (code "65") (name "TX") (class "Default")
      (node (ref "U1") (pin "34") (pinfunction "RXD0_34") (pintype "unspecified"))
      (node (ref "U2") (pin "2") (pinfunction "TXD_2") (pintype "unspecified"))
    )
    (net (code "66") (name "USB_5V") (class "Default")
      (node (ref "D55") (pin "5") (pinfunction "VBUS_5") (pintype "unspecified"))
      (node (ref "U18") (pin "2") (pinfunction "2_2") (pintype "unspecified"))
      (node (ref "USBC1") (pin "A4B9") (pinfunction "VBUS_A4B9") (pintype "unspecified"))
      (node (ref "USBC1") (pin "B4A9") (pinfunction "VBUS_B4A9") (pintype "unspecified"))
    )
    (net (code "67") (name "unconnected-(SW1-C-Pad3)") (class "Default")
      (node (ref "SW1") (pin "3") (pinfunction "C_3") (pintype "unspecified+no_connect"))
    )
    (net (code "68") (name "unconnected-(SW2-A-Pad1)") (class "Default")
      (node (ref "SW2") (pin "1") (pinfunction "A_1") (pintype "unspecified+no_connect"))
    )
    (net (code "69") (name "unconnected-(SW2-D-Pad4)") (class "Default")
      (node (ref "SW2") (pin "4") (pinfunction "D_4") (pintype "unspecified+no_connect"))
    )
    (net (code "70") (name "unconnected-(U1-IO2-Pad24)") (class "Default")
      (node (ref "U1") (pin "24") (pinfunction "IO2_24") (pintype "unspecified+no_connect"))
    )
    (net (code "71") (name "unconnected-(U1-IO4-Pad26)") (class "Default")
      (node (ref "U1") (pin "26") (pinfunction "IO4_26") (pintype "unspecified+no_connect"))
    )
    (net (code "72") (name "unconnected-(U1-IO5-Pad29)") (class "Default")
      (node (ref "U1") (pin "29") (pinfunction "IO5_29") (pintype "unspecified+no_connect"))
    )
    (net (code "73") (name "unconnected-(U1-IO15-Pad23)") (class "Default")
      (node (ref "U1") (pin "23") (pinfunction "IO15_23") (pintype "unspecified+no_connect"))
    )
    (net (code "74") (name "unconnected-(U1-IO17-Pad28)") (class "Default")
      (node (ref "U1") (pin "28") (pinfunction "IO17_28") (pintype "unspecified+no_connect"))
    )
    (net (code "75") (name "unconnected-(U1-IO18-Pad30)") (class "Default")
      (node (ref "U1") (pin "30") (pinfunction "IO18_30") (pintype "unspecified+no_connect"))
    )
    (net (code "76") (name "unconnected-(U1-IO19-Pad31)") (class "Default")
      (node (ref "U1") (pin "31") (pinfunction "IO19_31") (pintype "unspecified+no_connect"))
    )
    (net (code "77") (name "unconnected-(U1-IO34-Pad6)") (class "Default")
      (node (ref "U1") (pin "6") (pinfunction "IO34_6") (pintype "unspecified+no_connect"))
    )
    (net (code "78") (name "unconnected-(U1-IO35-Pad7)") (class "Default")
      (node (ref "U1") (pin "7") (pinfunction "IO35_7") (pintype "unspecified+no_connect"))
    )
    (net (code "79") (name "unconnected-(U1-NC-Pad17)") (class "Default")
      (node (ref "U1") (pin "17") (pinfunction "NC_17") (pintype "unspecified+no_connect"))
    )
    (net (code "80") (name "unconnected-(U1-NC-Pad18)") (class "Default")
      (node (ref "U1") (pin "18") (pinfunction "NC_18") (pintype "unspecified+no_connect"))
    )
    (net (code "81") (name "unconnected-(U1-NC-Pad19)") (class "Default")
      (node (ref "U1") (pin "19") (pinfunction "NC_19") (pintype "unspecified+no_connect"))
    )
    (net (code "82") (name "unconnected-(U1-NC-Pad20)") (class "Default")
      (node (ref "U1") (pin "20") (pinfunction "NC_20") (pintype "unspecified+no_connect"))
    )
    (net (code "83") (name "unconnected-(U1-NC-Pad21)") (class "Default")
      (node (ref "U1") (pin "21") (pinfunction "NC_21") (pintype "unspecified+no_connect"))
    )
    (net (code "84") (name "unconnected-(U1-NC-Pad22)") (class "Default")
      (node (ref "U1") (pin "22") (pinfunction "NC_22") (pintype "unspecified+no_connect"))
    )
    (net (code "85") (name "unconnected-(U1-NC-Pad32)") (class "Default")
      (node (ref "U1") (pin "32") (pinfunction "NC_32") (pintype "unspecified+no_connect"))
    )
    (net (code "86") (name "unconnected-(U1-SENSOR_VN-Pad5)") (class "Default")
      (node (ref "U1") (pin "5") (pinfunction "SENSOR_VN_5") (pintype "unspecified+no_connect"))
    )
    (net (code "87") (name "unconnected-(U1-SENSOR_VP-Pad4)") (class "Default")
      (node (ref "U1") (pin "4") (pinfunction "SENSOR_VP_4") (pintype "unspecified+no_connect"))
    )
    (net (code "88") (name "unconnected-(U2-CTS#-Pad9)") (class "Default")
      (node (ref "U2") (pin "9") (pinfunction "CTS#_9") (pintype "unspecified+no_connect"))
    )
    (net (code "89") (name "unconnected-(U2-DCD#-Pad12)") (class "Default")
      (node (ref "U2") (pin "12") (pinfunction "DCD#_12") (pintype "unspecified+no_connect"))
    )
    (net (code "90") (name "unconnected-(U2-DSR#-Pad10)") (class "Default")
      (node (ref "U2") (pin "10") (pinfunction "DSR#_10") (pintype "unspecified+no_connect"))
    )
    (net (code "91") (name "unconnected-(U2-NC.-Pad7)") (class "Default")
      (node (ref "U2") (pin "7") (pinfunction "NC._7") (pintype "unspecified+no_connect"))
    )
    (net (code "92") (name "unconnected-(U2-OUT#-Pad8)") (class "Default")
      (node (ref "U2") (pin "8") (pinfunction "OUT#_8") (pintype "unspecified+no_connect"))
    )
    (net (code "93") (name "unconnected-(U2-R232-Pad15)") (class "Default")
      (node (ref "U2") (pin "15") (pinfunction "R232_15") (pintype "unspecified+no_connect"))
    )
    (net (code "94") (name "unconnected-(U2-RI#-Pad11)") (class "Default")
      (node (ref "U2") (pin "11") (pinfunction "RI#_11") (pintype "unspecified+no_connect"))
    )
    (net (code "95") (name "unconnected-(USBC1-SBU1-PadA8)") (class "Default")
      (node (ref "USBC1") (pin "A8") (pinfunction "SBU1_A8") (pintype "unspecified+no_connect"))
    )
    (net (code "96") (name "unconnected-(USBC1-SBU2-PadB8)") (class "Default")
      (node (ref "USBC1") (pin "B8") (pinfunction "SBU2_B8") (pintype "unspecified+no_connect"))
    )
  )
)
